# SCH_esp32_2022-05-23.net
KiCad netlist of a schematic drawn in EasyEDA
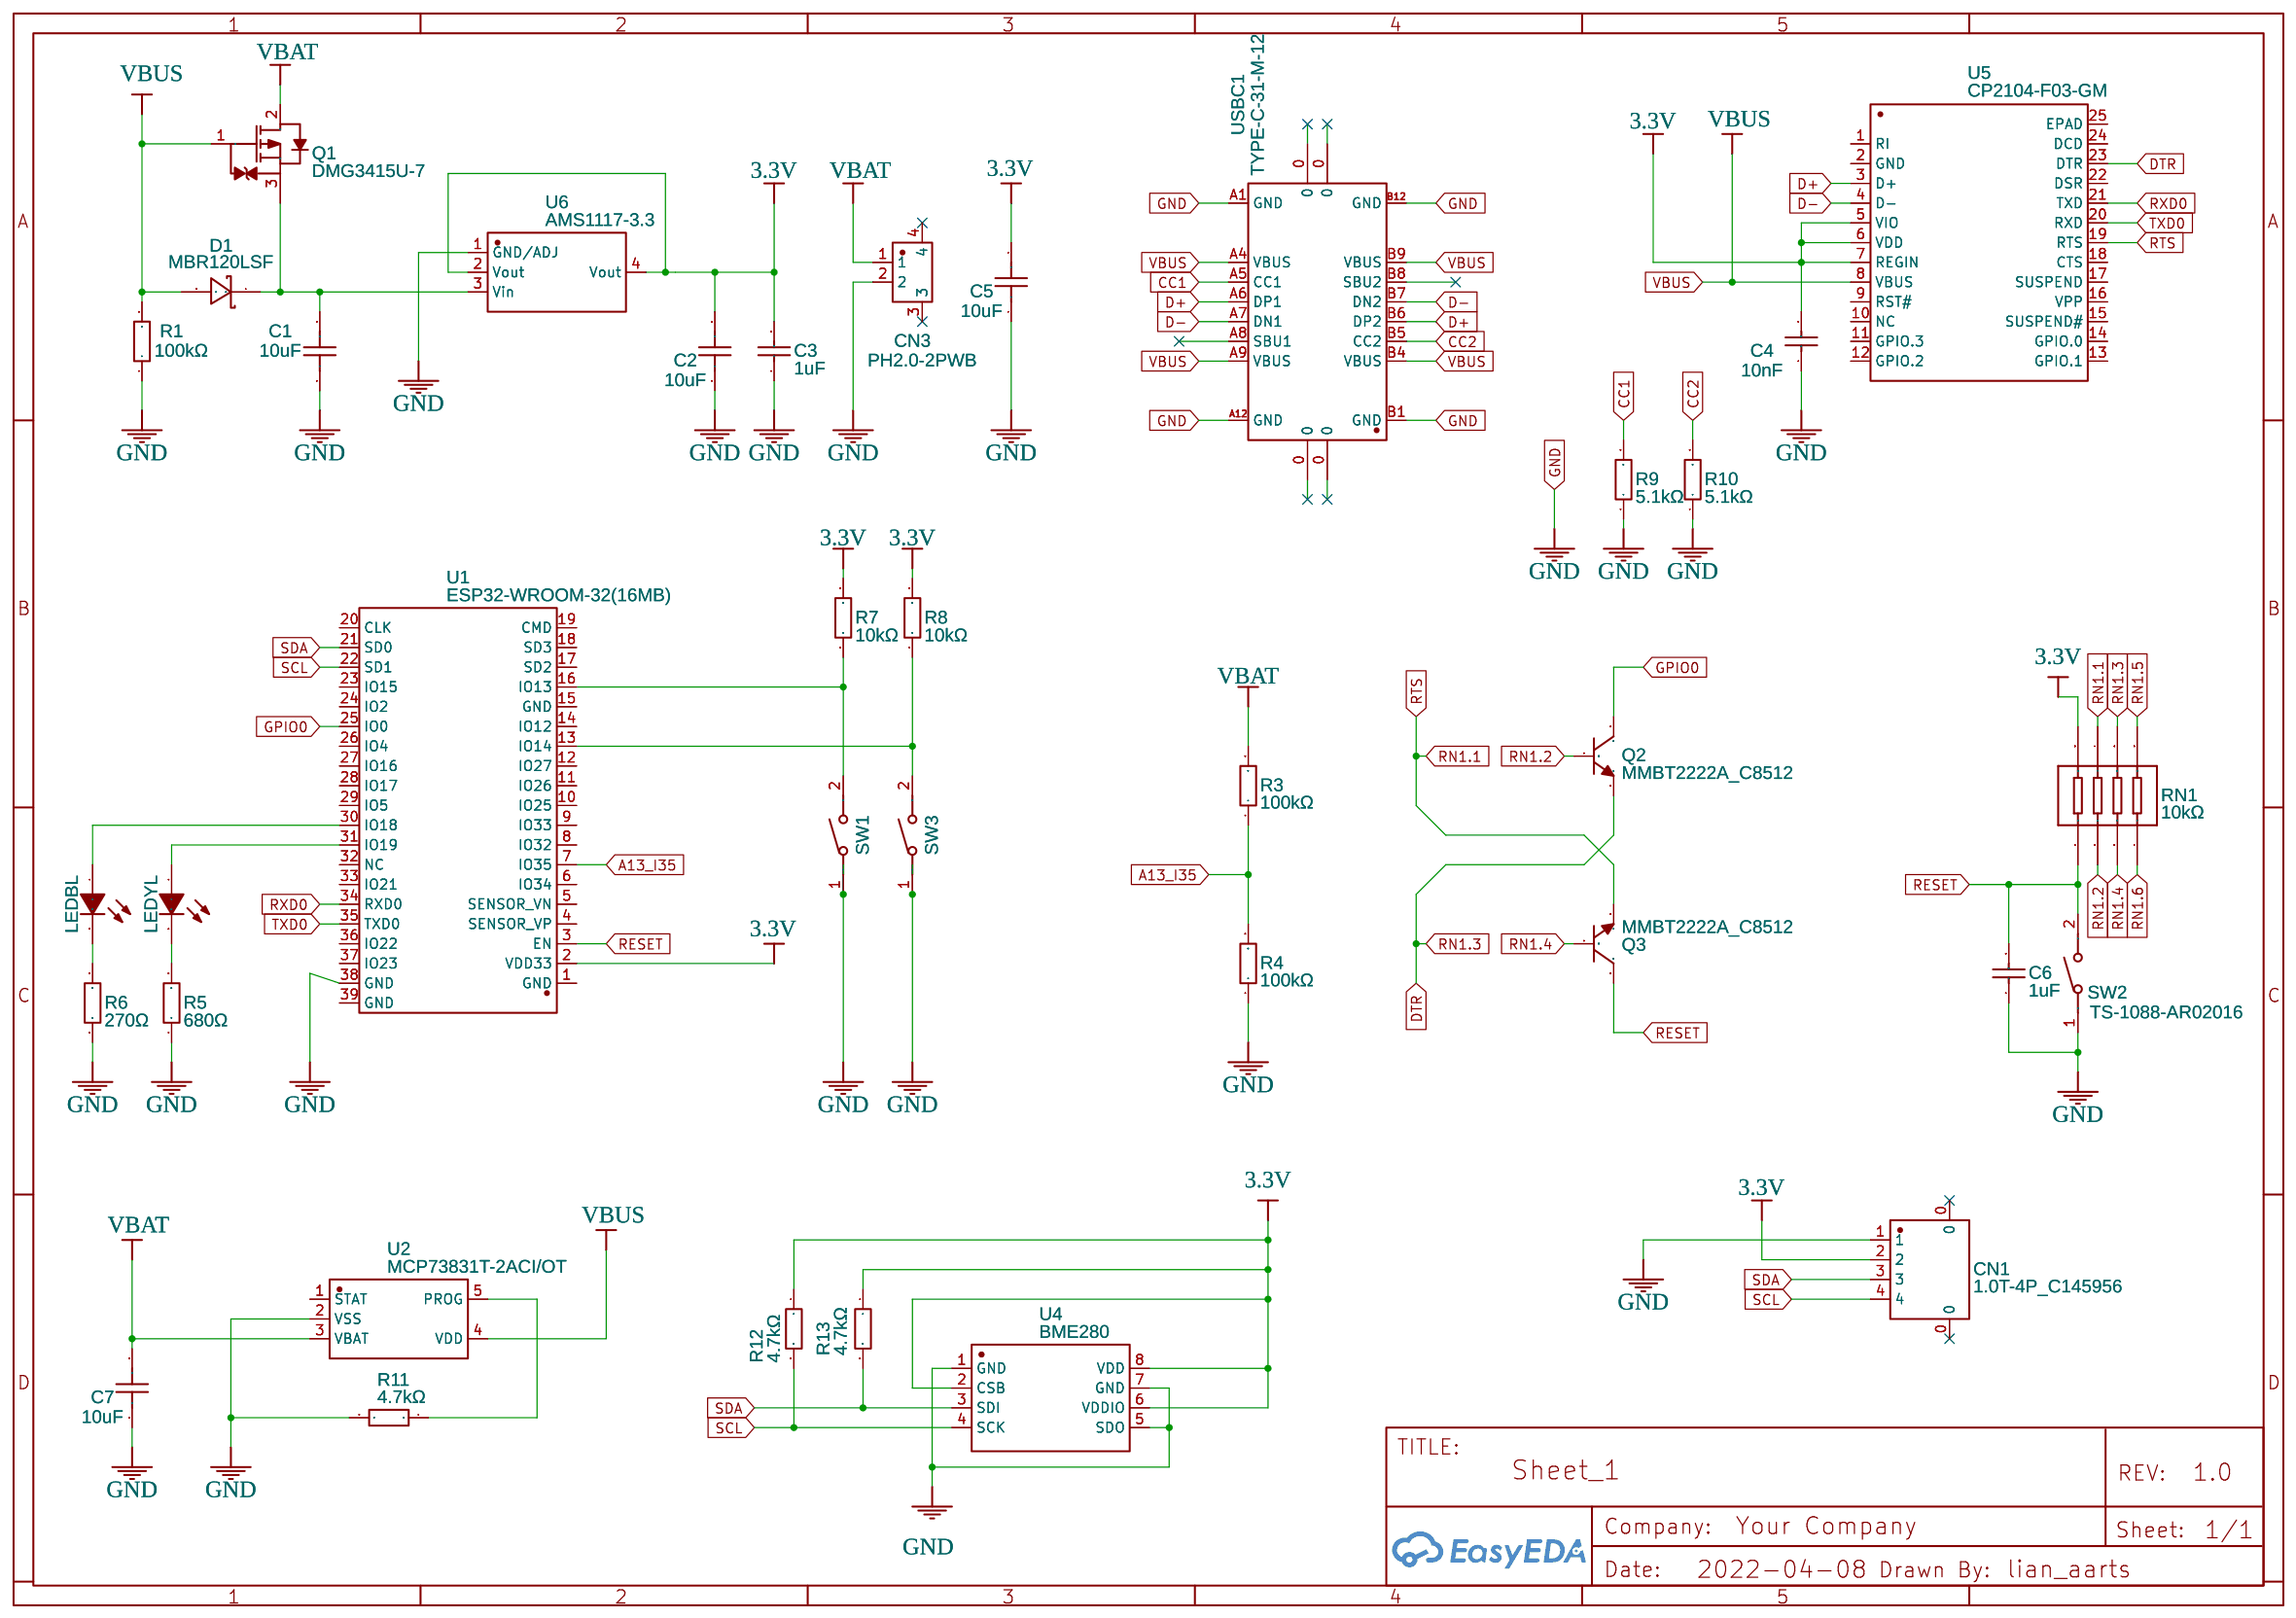
[diagram p0: schematic sheet]

(export (version "E")
  (design (tool "Eeschema 10.0.6"))
  (components
    (comp (ref "C1")
      (value "10uF")
      (fields
        (field (name "BOM_Manufacturer Part") "GRM21BR61H106KE43L")
        (field (name "BOM_Supplier Part") "C440198")
      )
      (libsource (lib "") (part "GRM21BR61H106KE43L"))
    )
    (comp (ref "C2")
      (value "10uF")
      (fields
        (field (name "BOM_Manufacturer Part") "GRM21BR61H106KE43L")
        (field (name "BOM_Supplier Part") "C440198")
      )
      (libsource (lib "") (part "GRM21BR61H106KE43L"))
    )
    (comp (ref "C3")
      (value "1uF")
      (fields
        (field (name "BOM_Manufacturer Part") "CL10A105KB8NNNC")
        (field (name "BOM_Supplier Part") "C15849")
      )
      (libsource (lib "") (part "CL10A105KB8NNNC"))
    )
    (comp (ref "C4")
      (value "10nF")
      (fields
        (field (name "BOM_Manufacturer Part") "CL21B103KBANNNC")
        (field (name "BOM_Supplier Part") "C1710")
      )
      (libsource (lib "") (part "CL21B103KBANNNC"))
    )
    (comp (ref "C5")
      (value "10uF")
      (fields
        (field (name "BOM_Manufacturer Part") "GRM21BR61H106KE43L")
        (field (name "BOM_Supplier Part") "C440198")
      )
      (libsource (lib "") (part "GRM21BR61H106KE43L"))
    )
    (comp (ref "C6")
      (value "1uF")
      (fields
        (field (name "BOM_Manufacturer Part") "CL10A105KB8NNNC")
        (field (name "BOM_Supplier Part") "C15849")
      )
      (libsource (lib "") (part "CL10A105KB8NNNC"))
    )
    (comp (ref "C7")
      (value "10uF")
      (fields
        (field (name "BOM_Manufacturer Part") "GRM21BR61H106KE43L")
        (field (name "BOM_Supplier Part") "C440198")
      )
      (libsource (lib "") (part "GRM21BR61H106KE43L"))
    )
    (comp (ref "CN1")
      (value "1.0T-4P_C145956")
      (fields (field (name "BOM_Supplier Part") "C145956"))
      (libsource (lib "") (part "1.0T-4P_C145956"))
    )
    (comp (ref "CN3")
      (value "PH2.0-2PWB")
      (fields
        (field (name "BOM_Manufacturer Part") "PH2.0-2PWB Horizontal")
        (field (name "BOM_Supplier Part") "C47647")
      )
      (libsource (lib "") (part "PH2.0-2PWB"))
    )
    (comp (ref "D1")
      (value "MBR120LSF")
      (fields (field (name "BOM_Supplier Part") "C130880"))
      (libsource (lib "") (part "MBR120LSF"))
    )
    (comp (ref "LEDBL")
      (value "19-217/BHC-ZL1M2RY/3T")
      (fields (field (name "BOM_Supplier Part") "C72041"))
      (libsource (lib "") (part "19-217/BHC-ZL1M2RY/3T"))
    )
    (comp (ref "LEDYL")
      (value "19-213/Y2C-CQ2R2L/3T(CY)")
      (fields (field (name "BOM_Supplier Part") "C72038"))
      (libsource (lib "") (part "19-213/Y2C-CQ2R2L/3T(CY)"))
    )
    (comp (ref "Q1")
      (value "DMG3415U-7")
      (fields (field (name "BOM_Supplier Part") "C96616"))
      (libsource (lib "") (part "DMG3415U-7"))
    )
    (comp (ref "Q2")
      (value "MMBT2222A_C8512")
      (fields (field (name "BOM_Manufacturer Part") "MMBT2222A") (field (name "BOM_Supplier Part") "C8512"))
      (libsource (lib "") (part "MMBT2222A_C8512"))
    )
    (comp (ref "Q3")
      (value "MMBT2222A_C8512")
      (fields (field (name "BOM_Manufacturer Part") "MMBT2222A") (field (name "BOM_Supplier Part") "C8512"))
      (libsource (lib "") (part "MMBT2222A_C8512_1"))
    )
    (comp (ref "R1")
      (value "100kΩ")
      (fields
        (field (name "BOM_Manufacturer Part") "0603WAF1003T5E")
        (field (name "BOM_Supplier Part") "C25803")
      )
      (libsource (lib "") (part "0603WAF1003T5E"))
    )
    (comp (ref "R3")
      (value "100kΩ")
      (fields
        (field (name "BOM_Manufacturer Part") "0603WAF1003T5E")
        (field (name "BOM_Supplier Part") "C25803")
      )
      (libsource (lib "") (part "0603WAF1003T5E"))
    )
    (comp (ref "R4")
      (value "100kΩ")
      (fields
        (field (name "BOM_Manufacturer Part") "0603WAF1003T5E")
        (field (name "BOM_Supplier Part") "C25803")
      )
      (libsource (lib "") (part "0603WAF1003T5E"))
    )
    (comp (ref "R5")
      (value "680Ω")
      (fields
        (field (name "BOM_Manufacturer Part") "0603WAF6800T5E")
        (field (name "BOM_Supplier Part") "C23228")
      )
      (libsource (lib "") (part "0603WAF6800T5E"))
    )
    (comp (ref "R6")
      (value "270Ω")
      (fields
        (field (name "BOM_Manufacturer Part") "0603WAF2700T5E")
        (field (name "BOM_Supplier Part") "C22966")
      )
      (libsource (lib "") (part "0603WAF2700T5E"))
    )
    (comp (ref "R7")
      (value "10kΩ")
      (fields
        (field (name "BOM_Manufacturer Part") "0603WAF1002T5E")
        (field (name "BOM_Supplier Part") "C25804")
      )
      (libsource (lib "") (part "0603WAF1002T5E"))
    )
    (comp (ref "R8")
      (value "10kΩ")
      (fields
        (field (name "BOM_Manufacturer Part") "0603WAF1002T5E")
        (field (name "BOM_Supplier Part") "C25804")
      )
      (libsource (lib "") (part "0603WAF1002T5E"))
    )
    (comp (ref "R9")
      (value "5.1kΩ")
      (fields
        (field (name "BOM_Manufacturer Part") "0603WAF5101T5E")
        (field (name "BOM_Supplier Part") "C23186")
      )
      (libsource (lib "") (part "0603WAF5101T5E"))
    )
    (comp (ref "R10")
      (value "5.1kΩ")
      (fields
        (field (name "BOM_Manufacturer Part") "0603WAF5101T5E")
        (field (name "BOM_Supplier Part") "C23186")
      )
      (libsource (lib "") (part "0603WAF5101T5E"))
    )
    (comp (ref "R11")
      (value "4.7kΩ")
      (fields
        (field (name "BOM_Manufacturer Part") "0603WAF4701T5E")
        (field (name "BOM_Supplier Part") "C23162")
      )
      (libsource (lib "") (part "0603WAF4701T5E_1"))
    )
    (comp (ref "R12")
      (value "4.7kΩ")
      (fields
        (field (name "BOM_Manufacturer Part") "0603WAF4701T5E")
        (field (name "BOM_Supplier Part") "C23162")
      )
      (libsource (lib "") (part "0603WAF4701T5E"))
    )
    (comp (ref "R13")
      (value "4.7kΩ")
      (fields
        (field (name "BOM_Manufacturer Part") "0603WAF4701T5E")
        (field (name "BOM_Supplier Part") "C23162")
      )
      (libsource (lib "") (part "0603WAF4701T5E"))
    )
    (comp (ref "RN1")
      (value "10kΩ")
      (fields
        (field (name "BOM_Manufacturer Part") "RTA03-4D103JTP")
        (field (name "BOM_Supplier Part") "C102646")
      )
      (libsource (lib "") (part "RTA03-4D103JTP"))
    )
    (comp (ref "SW1")
      (value "TS-1088-AR02016")
      (fields (field (name "BOM_Supplier Part") "C720477"))
      (libsource (lib "") (part "TS-1088-AR02016"))
    )
    (comp (ref "SW2")
      (value "TS-1088-AR02016")
      (fields (field (name "BOM_Supplier Part") "C720477"))
      (libsource (lib "") (part "TS-1088-AR02016"))
    )
    (comp (ref "SW3")
      (value "TS-1088-AR02016")
      (fields (field (name "BOM_Supplier Part") "C720477"))
      (libsource (lib "") (part "TS-1088-AR02016"))
    )
    (comp (ref "U1")
      (value "ESP32-WROOM-32(16MB)")
      (fields (field (name "BOM_Supplier Part") "C529581"))
      (libsource (lib "") (part "ESP32-WROOM-32(16MB)"))
    )
    (comp (ref "U2")
      (value "MCP73831T-2ACI/OT")
      (fields (field (name "BOM_Supplier Part") "C424093"))
      (libsource (lib "") (part "MCP73831T-2ACI/OT"))
    )
    (comp (ref "U4")
      (value "BME280")
      (fields (field (name "BOM_Supplier Part") "C92489"))
      (libsource (lib "") (part "BME280"))
    )
    (comp (ref "U5")
      (value "CP2104-F03-GM")
      (fields (field (name "BOM_Supplier Part") "C47742"))
      (libsource (lib "") (part "CP2104-F03-GM"))
    )
    (comp (ref "U6")
      (value "AMS1117-3.3")
      (fields (field (name "BOM_Supplier Part") "C6186"))
      (libsource (lib "") (part "AMS1117-3.3"))
    )
    (comp (ref "USBC1")
      (value "TYPE-C-31-M-12")
      (fields (field (name "BOM_Supplier Part") "C165948"))
      (libsource (lib "") (part "TYPE-C-31-M-12"))
    )
  )
  (nets
    (net (code "1") (name "3.3V") (class "Default")
      (node (ref "C2") (pin "2") (pinfunction "2_2") (pintype "unspecified"))
      (node (ref "C3") (pin "2") (pinfunction "2_2") (pintype "input"))
      (node (ref "C4") (pin "2") (pinfunction "2_2") (pintype "input"))
      (node (ref "C5") (pin "2") (pinfunction "2_2") (pintype "unspecified"))
      (node (ref "CN1") (pin "2") (pinfunction "2_2") (pintype "unspecified"))
      (node (ref "R12") (pin "1") (pinfunction "1_1") (pintype "input"))
      (node (ref "R13") (pin "1") (pinfunction "1_1") (pintype "input"))
      (node (ref "R7") (pin "2") (pinfunction "2_2") (pintype "input"))
      (node (ref "R8") (pin "2") (pinfunction "2_2") (pintype "input"))
      (node (ref "RN1") (pin "8") (pinfunction "8_8") (pintype "input"))
      (node (ref "U1") (pin "2") (pinfunction "VDD33_2") (pintype "unspecified"))
      (node (ref "U4") (pin "2") (pinfunction "CSB_2") (pintype "unspecified"))
      (node (ref "U4") (pin "6") (pinfunction "VDDIO_6") (pintype "unspecified"))
      (node (ref "U4") (pin "8") (pinfunction "VDD_8") (pintype "unspecified"))
      (node (ref "U5") (pin "5") (pinfunction "VIO_5") (pintype "unspecified"))
      (node (ref "U5") (pin "6") (pinfunction "VDD_6") (pintype "unspecified"))
      (node (ref "U5") (pin "7") (pinfunction "REGIN_7") (pintype "unspecified"))
      (node (ref "U6") (pin "2") (pinfunction "Vout_2") (pintype "unspecified"))
      (node (ref "U6") (pin "4") (pinfunction "Vout_4") (pintype "unspecified"))
    )
    (net (code "2") (name "A13_I35") (class "Default")
      (node (ref "R3") (pin "1") (pinfunction "1_1") (pintype "input"))
      (node (ref "R4") (pin "2") (pinfunction "2_2") (pintype "input"))
      (node (ref "U1") (pin "7") (pinfunction "IO35_7") (pintype "unspecified"))
    )
    (net (code "3") (name "CC1") (class "Default")
      (node (ref "R9") (pin "2") (pinfunction "2_2") (pintype "input"))
      (node (ref "USBC1") (pin "A5") (pinfunction "CC1_A5") (pintype "unspecified"))
    )
    (net (code "4") (name "CC2") (class "Default")
      (node (ref "R10") (pin "2") (pinfunction "2_2") (pintype "input"))
      (node (ref "USBC1") (pin "B5") (pinfunction "CC2_B5") (pintype "unspecified"))
    )
    (net (code "5") (name "D+") (class "Default")
      (node (ref "U5") (pin "3") (pinfunction "D+_3") (pintype "unspecified"))
      (node (ref "USBC1") (pin "A6") (pinfunction "DP1_A6") (pintype "unspecified"))
      (node (ref "USBC1") (pin "B6") (pinfunction "DP2_B6") (pintype "unspecified"))
    )
    (net (code "6") (name "D-") (class "Default")
      (node (ref "U5") (pin "4") (pinfunction "D-_4") (pintype "unspecified"))
      (node (ref "USBC1") (pin "A7") (pinfunction "DN1_A7") (pintype "unspecified"))
      (node (ref "USBC1") (pin "B7") (pinfunction "DN2_B7") (pintype "unspecified"))
    )
    (net (code "7") (name "DTR") (class "Default")
      (node (ref "Q2") (pin "2") (pinfunction "E_2") (pintype "unspecified"))
      (node (ref "RN1") (pin "6") (pinfunction "6_6") (pintype "input"))
      (node (ref "U5") (pin "23") (pinfunction "DTR_23") (pintype "unspecified"))
    )
    (net (code "8") (name "GND") (class "Default")
      (node (ref "C1") (pin "1") (pinfunction "1_1") (pintype "unspecified"))
      (node (ref "C2") (pin "1") (pinfunction "1_1") (pintype "unspecified"))
      (node (ref "C3") (pin "1") (pinfunction "1_1") (pintype "input"))
      (node (ref "C4") (pin "1") (pinfunction "1_1") (pintype "input"))
      (node (ref "C5") (pin "1") (pinfunction "1_1") (pintype "unspecified"))
      (node (ref "C6") (pin "1") (pinfunction "1_1") (pintype "input"))
      (node (ref "C7") (pin "1") (pinfunction "1_1") (pintype "unspecified"))
      (node (ref "CN1") (pin "1") (pinfunction "1_1") (pintype "unspecified"))
      (node (ref "CN3") (pin "2") (pinfunction "2_2") (pintype "unspecified"))
      (node (ref "R1") (pin "1") (pinfunction "1_1") (pintype "input"))
      (node (ref "R10") (pin "1") (pinfunction "1_1") (pintype "input"))
      (node (ref "R11") (pin "2") (pinfunction "2_2") (pintype "input"))
      (node (ref "R4") (pin "1") (pinfunction "1_1") (pintype "input"))
      (node (ref "R5") (pin "1") (pinfunction "1_1") (pintype "input"))
      (node (ref "R6") (pin "1") (pinfunction "1_1") (pintype "input"))
      (node (ref "R9") (pin "1") (pinfunction "1_1") (pintype "input"))
      (node (ref "SW1") (pin "1") (pinfunction "1_1") (pintype "unspecified"))
      (node (ref "SW2") (pin "1") (pinfunction "1_1") (pintype "unspecified"))
      (node (ref "SW3") (pin "1") (pinfunction "1_1") (pintype "unspecified"))
      (node (ref "U1") (pin "38") (pinfunction "GND_38") (pintype "unspecified"))
      (node (ref "U2") (pin "2") (pinfunction "VSS_2") (pintype "unspecified"))
      (node (ref "U4") (pin "1") (pinfunction "GND_1") (pintype "unspecified"))
      (node (ref "U4") (pin "5") (pinfunction "SDO_5") (pintype "unspecified"))
      (node (ref "U4") (pin "7") (pinfunction "GND_7") (pintype "unspecified"))
      (node (ref "U6") (pin "1") (pinfunction "GND/ADJ_1") (pintype "unspecified"))
      (node (ref "USBC1") (pin "A1") (pinfunction "GND_A1") (pintype "unspecified"))
      (node (ref "USBC1") (pin "A12") (pinfunction "GND_A12") (pintype "unspecified"))
      (node (ref "USBC1") (pin "B1") (pinfunction "GND_B1") (pintype "unspecified"))
      (node (ref "USBC1") (pin "B12") (pinfunction "GND_B12") (pintype "unspecified"))
    )
    (net (code "9") (name "GPIO0") (class "Default")
      (node (ref "Q2") (pin "3") (pinfunction "C_3") (pintype "unspecified"))
      (node (ref "U1") (pin "25") (pinfunction "IO0_25") (pintype "unspecified"))
    )
    (net (code "10") (name "Net-(D1-C)") (class "Default")
      (node (ref "C1") (pin "2") (pinfunction "2_2") (pintype "unspecified"))
      (node (ref "D1") (pin "1") (pinfunction "C_1") (pintype "unspecified"))
      (node (ref "Q1") (pin "3") (pinfunction "S_3") (pintype "unspecified"))
      (node (ref "U6") (pin "3") (pinfunction "Vin_3") (pintype "unspecified"))
    )
    (net (code "11") (name "Net-(LEDBL-A)") (class "Default")
      (node (ref "LEDBL") (pin "1") (pinfunction "A_1") (pintype "input"))
      (node (ref "U1") (pin "30") (pinfunction "IO18_30") (pintype "unspecified"))
    )
    (net (code "12") (name "Net-(LEDBL-C)") (class "Default")
      (node (ref "LEDBL") (pin "2") (pinfunction "C_2") (pintype "input"))
      (node (ref "R6") (pin "2") (pinfunction "2_2") (pintype "input"))
    )
    (net (code "13") (name "Net-(LEDYL-A)") (class "Default")
      (node (ref "LEDYL") (pin "1") (pinfunction "A_1") (pintype "input"))
      (node (ref "U1") (pin "31") (pinfunction "IO19_31") (pintype "unspecified"))
    )
    (net (code "14") (name "Net-(LEDYL-C)") (class "Default")
      (node (ref "LEDYL") (pin "2") (pinfunction "C_2") (pintype "input"))
      (node (ref "R5") (pin "2") (pinfunction "2_2") (pintype "input"))
    )
    (net (code "15") (name "Net-(U1-IO13)") (class "Default")
      (node (ref "R7") (pin "1") (pinfunction "1_1") (pintype "input"))
      (node (ref "SW1") (pin "2") (pinfunction "2_2") (pintype "unspecified"))
      (node (ref "U1") (pin "16") (pinfunction "IO13_16") (pintype "unspecified"))
    )
    (net (code "16") (name "Net-(U1-IO14)") (class "Default")
      (node (ref "R8") (pin "1") (pinfunction "1_1") (pintype "input"))
      (node (ref "SW3") (pin "2") (pinfunction "2_2") (pintype "unspecified"))
      (node (ref "U1") (pin "13") (pinfunction "IO14_13") (pintype "unspecified"))
    )
    (net (code "17") (name "Net-(U2-PROG)") (class "Default")
      (node (ref "R11") (pin "1") (pinfunction "1_1") (pintype "input"))
      (node (ref "U2") (pin "5") (pinfunction "PROG_5") (pintype "unspecified"))
    )
    (net (code "18") (name "RESET") (class "Default")
      (node (ref "C6") (pin "2") (pinfunction "2_2") (pintype "input"))
      (node (ref "Q3") (pin "3") (pinfunction "C_3") (pintype "unspecified"))
      (node (ref "RN1") (pin "1") (pinfunction "1_1") (pintype "input"))
      (node (ref "SW2") (pin "2") (pinfunction "2_2") (pintype "unspecified"))
      (node (ref "U1") (pin "3") (pinfunction "EN_3") (pintype "unspecified"))
    )
    (net (code "19") (name "RN1.1") (class "Default")
      (node (ref "Q3") (pin "2") (pinfunction "E_2") (pintype "unspecified"))
      (node (ref "RN1") (pin "7") (pinfunction "7_7") (pintype "input"))
      (node (ref "U5") (pin "19") (pinfunction "RTS_19") (pintype "unspecified"))
    )
    (net (code "20") (name "RN1.2") (class "Default")
      (node (ref "Q2") (pin "1") (pinfunction "B_1") (pintype "unspecified"))
      (node (ref "RN1") (pin "2") (pinfunction "2_2") (pintype "input"))
    )
    (net (code "21") (name "RN1.4") (class "Default")
      (node (ref "Q3") (pin "1") (pinfunction "B_1") (pintype "unspecified"))
      (node (ref "RN1") (pin "3") (pinfunction "3_3") (pintype "input"))
    )
    (net (code "22") (name "RN1.5") (class "Default")
      (node (ref "RN1") (pin "5") (pinfunction "5_5") (pintype "input"))
    )
    (net (code "23") (name "RN1.6") (class "Default")
      (node (ref "RN1") (pin "4") (pinfunction "4_4") (pintype "input"))
    )
    (net (code "24") (name "RXD0") (class "Default")
      (node (ref "U1") (pin "34") (pinfunction "RXD0_34") (pintype "unspecified"))
      (node (ref "U5") (pin "21") (pinfunction "TXD_21") (pintype "unspecified"))
    )
    (net (code "25") (name "SCL") (class "Default")
      (node (ref "CN1") (pin "4") (pinfunction "4_4") (pintype "unspecified"))
      (node (ref "R12") (pin "2") (pinfunction "2_2") (pintype "input"))
      (node (ref "U1") (pin "22") (pinfunction "SD1_22") (pintype "unspecified"))
      (node (ref "U4") (pin "4") (pinfunction "SCK_4") (pintype "unspecified"))
    )
    (net (code "26") (name "SDA") (class "Default")
      (node (ref "CN1") (pin "3") (pinfunction "3_3") (pintype "unspecified"))
      (node (ref "R13") (pin "2") (pinfunction "2_2") (pintype "input"))
      (node (ref "U1") (pin "21") (pinfunction "SD0_21") (pintype "unspecified"))
      (node (ref "U4") (pin "3") (pinfunction "SDI_3") (pintype "unspecified"))
    )
    (net (code "27") (name "TXD0") (class "Default")
      (node (ref "U1") (pin "35") (pinfunction "TXD0_35") (pintype "unspecified"))
      (node (ref "U5") (pin "20") (pinfunction "RXD_20") (pintype "unspecified"))
    )
    (net (code "28") (name "VBAT") (class "Default")
      (node (ref "C7") (pin "2") (pinfunction "2_2") (pintype "unspecified"))
      (node (ref "CN3") (pin "1") (pinfunction "1_1") (pintype "unspecified"))
      (node (ref "Q1") (pin "2") (pinfunction "D_2") (pintype "unspecified"))
      (node (ref "R3") (pin "2") (pinfunction "2_2") (pintype "input"))
      (node (ref "U2") (pin "3") (pinfunction "VBAT_3") (pintype "unspecified"))
    )
    (net (code "29") (name "VBUS") (class "Default")
      (node (ref "D1") (pin "2") (pinfunction "A_2") (pintype "unspecified"))
      (node (ref "Q1") (pin "1") (pinfunction "G_1") (pintype "unspecified"))
      (node (ref "R1") (pin "2") (pinfunction "2_2") (pintype "input"))
      (node (ref "U2") (pin "4") (pinfunction "VDD_4") (pintype "unspecified"))
      (node (ref "U5") (pin "8") (pinfunction "VBUS_8") (pintype "unspecified"))
      (node (ref "USBC1") (pin "A4") (pinfunction "VBUS_A4") (pintype "unspecified"))
      (node (ref "USBC1") (pin "A9") (pinfunction "VBUS_A9") (pintype "unspecified"))
      (node (ref "USBC1") (pin "B4") (pinfunction "VBUS_B4") (pintype "unspecified"))
      (node (ref "USBC1") (pin "B9") (pinfunction "VBUS_B9") (pintype "unspecified"))
    )
    (net (code "30") (name "unconnected-(CN1-Pad0)") (class "Default")
      (node (ref "CN1") (pin "0") (pinfunction "0_0") (pintype "unspecified+no_connect"))
    )
    (net (code "31") (name "unconnected-(CN1-Pad0)_1") (class "Default")
      (node (ref "CN1") (pin "0") (pinfunction "0_0") (pintype "unspecified+no_connect"))
    )
    (net (code "32") (name "unconnected-(CN3-Pad3)") (class "Default")
      (node (ref "CN3") (pin "3") (pinfunction "3_3") (pintype "unspecified+no_connect"))
    )
    (net (code "33") (name "unconnected-(CN3-Pad4)") (class "Default")
      (node (ref "CN3") (pin "4") (pinfunction "4_4") (pintype "unspecified+no_connect"))
    )
    (net (code "34") (name "unconnected-(U1-CLK-Pad20)") (class "Default")
      (node (ref "U1") (pin "20") (pinfunction "CLK_20") (pintype "unspecified"))
    )
    (net (code "35") (name "unconnected-(U1-CMD-Pad19)") (class "Default")
      (node (ref "U1") (pin "19") (pinfunction "CMD_19") (pintype "unspecified"))
    )
    (net (code "36") (name "unconnected-(U1-GND-Pad1)") (class "Default")
      (node (ref "U1") (pin "1") (pinfunction "GND_1") (pintype "unspecified"))
    )
    (net (code "37") (name "unconnected-(U1-GND-Pad15)") (class "Default")
      (node (ref "U1") (pin "15") (pinfunction "GND_15") (pintype "unspecified"))
    )
    (net (code "38") (name "unconnected-(U1-GND-Pad39)") (class "Default")
      (node (ref "U1") (pin "39") (pinfunction "GND_39") (pintype "unspecified"))
    )
    (net (code "39") (name "unconnected-(U1-IO2-Pad24)") (class "Default")
      (node (ref "U1") (pin "24") (pinfunction "IO2_24") (pintype "unspecified"))
    )
    (net (code "40") (name "unconnected-(U1-IO4-Pad26)") (class "Default")
      (node (ref "U1") (pin "26") (pinfunction "IO4_26") (pintype "unspecified"))
    )
    (net (code "41") (name "unconnected-(U1-IO5-Pad29)") (class "Default")
      (node (ref "U1") (pin "29") (pinfunction "IO5_29") (pintype "unspecified"))
    )
    (net (code "42") (name "unconnected-(U1-IO12-Pad14)") (class "Default")
      (node (ref "U1") (pin "14") (pinfunction "IO12_14") (pintype "unspecified"))
    )
    (net (code "43") (name "unconnected-(U1-IO15-Pad23)") (class "Default")
      (node (ref "U1") (pin "23") (pinfunction "IO15_23") (pintype "unspecified"))
    )
    (net (code "44") (name "unconnected-(U1-IO16-Pad27)") (class "Default")
      (node (ref "U1") (pin "27") (pinfunction "IO16_27") (pintype "unspecified"))
    )
    (net (code "45") (name "unconnected-(U1-IO17-Pad28)") (class "Default")
      (node (ref "U1") (pin "28") (pinfunction "IO17_28") (pintype "unspecified"))
    )
    (net (code "46") (name "unconnected-(U1-IO21-Pad33)") (class "Default")
      (node (ref "U1") (pin "33") (pinfunction "IO21_33") (pintype "unspecified"))
    )
    (net (code "47") (name "unconnected-(U1-IO22-Pad36)") (class "Default")
      (node (ref "U1") (pin "36") (pinfunction "IO22_36") (pintype "unspecified"))
    )
    (net (code "48") (name "unconnected-(U1-IO23-Pad37)") (class "Default")
      (node (ref "U1") (pin "37") (pinfunction "IO23_37") (pintype "unspecified"))
    )
    (net (code "49") (name "unconnected-(U1-IO25-Pad10)") (class "Default")
      (node (ref "U1") (pin "10") (pinfunction "IO25_10") (pintype "unspecified"))
    )
    (net (code "50") (name "unconnected-(U1-IO26-Pad11)") (class "Default")
      (node (ref "U1") (pin "11") (pinfunction "IO26_11") (pintype "unspecified"))
    )
    (net (code "51") (name "unconnected-(U1-IO27-Pad12)") (class "Default")
      (node (ref "U1") (pin "12") (pinfunction "IO27_12") (pintype "unspecified"))
    )
    (net (code "52") (name "unconnected-(U1-IO32-Pad8)") (class "Default")
      (node (ref "U1") (pin "8") (pinfunction "IO32_8") (pintype "unspecified"))
    )
    (net (code "53") (name "unconnected-(U1-IO33-Pad9)") (class "Default")
      (node (ref "U1") (pin "9") (pinfunction "IO33_9") (pintype "unspecified"))
    )
    (net (code "54") (name "unconnected-(U1-IO34-Pad6)") (class "Default")
      (node (ref "U1") (pin "6") (pinfunction "IO34_6") (pintype "unspecified"))
    )
    (net (code "55") (name "unconnected-(U1-NC-Pad32)") (class "Default")
      (node (ref "U1") (pin "32") (pinfunction "NC_32") (pintype "unspecified"))
    )
    (net (code "56") (name "unconnected-(U1-SD2-Pad17)") (class "Default")
      (node (ref "U1") (pin "17") (pinfunction "SD2_17") (pintype "unspecified"))
    )
    (net (code "57") (name "unconnected-(U1-SD3-Pad18)") (class "Default")
      (node (ref "U1") (pin "18") (pinfunction "SD3_18") (pintype "unspecified"))
    )
    (net (code "58") (name "unconnected-(U1-SENSOR_VN-Pad5)") (class "Default")
      (node (ref "U1") (pin "5") (pinfunction "SENSOR_VN_5") (pintype "unspecified"))
    )
    (net (code "59") (name "unconnected-(U1-SENSOR_VP-Pad4)") (class "Default")
      (node (ref "U1") (pin "4") (pinfunction "SENSOR_VP_4") (pintype "unspecified"))
    )
    (net (code "60") (name "unconnected-(U2-STAT-Pad1)") (class "Default")
      (node (ref "U2") (pin "1") (pinfunction "STAT_1") (pintype "unspecified"))
    )
    (net (code "61") (name "unconnected-(U5-CTS-Pad18)") (class "Default")
      (node (ref "U5") (pin "18") (pinfunction "CTS_18") (pintype "unspecified"))
    )
    (net (code "62") (name "unconnected-(U5-DCD-Pad24)") (class "Default")
      (node (ref "U5") (pin "24") (pinfunction "DCD_24") (pintype "unspecified"))
    )
    (net (code "63") (name "unconnected-(U5-DSR-Pad22)") (class "Default")
      (node (ref "U5") (pin "22") (pinfunction "DSR_22") (pintype "unspecified"))
    )
    (net (code "64") (name "unconnected-(U5-EPAD-Pad25)") (class "Default")
      (node (ref "U5") (pin "25") (pinfunction "EPAD_25") (pintype "unspecified"))
    )
    (net (code "65") (name "unconnected-(U5-GND-Pad2)") (class "Default")
      (node (ref "U5") (pin "2") (pinfunction "GND_2") (pintype "unspecified"))
    )
    (net (code "66") (name "unconnected-(U5-GPIO.0-Pad14)") (class "Default")
      (node (ref "U5") (pin "14") (pinfunction "GPIO.0_14") (pintype "unspecified"))
    )
    (net (code "67") (name "unconnected-(U5-GPIO.1-Pad13)") (class "Default")
      (node (ref "U5") (pin "13") (pinfunction "GPIO.1_13") (pintype "unspecified"))
    )
    (net (code "68") (name "unconnected-(U5-GPIO.2-Pad12)") (class "Default")
      (node (ref "U5") (pin "12") (pinfunction "GPIO.2_12") (pintype "unspecified"))
    )
    (net (code "69") (name "unconnected-(U5-GPIO.3-Pad11)") (class "Default")
      (node (ref "U5") (pin "11") (pinfunction "GPIO.3_11") (pintype "unspecified"))
    )
    (net (code "70") (name "unconnected-(U5-NC-Pad10)") (class "Default")
      (node (ref "U5") (pin "10") (pinfunction "NC_10") (pintype "unspecified"))
    )
    (net (code "71") (name "unconnected-(U5-RI-Pad1)") (class "Default")
      (node (ref "U5") (pin "1") (pinfunction "RI_1") (pintype "unspecified"))
    )
    (net (code "72") (name "unconnected-(U5-RST#-Pad9)") (class "Default")
      (node (ref "U5") (pin "9") (pinfunction "RST#_9") (pintype "unspecified"))
    )
    (net (code "73") (name "unconnected-(U5-SUSPEND#-Pad15)") (class "Default")
      (node (ref "U5") (pin "15") (pinfunction "SUSPEND#_15") (pintype "unspecified"))
    )
    (net (code "74") (name "unconnected-(U5-SUSPEND-Pad17)") (class "Default")
      (node (ref "U5") (pin "17") (pinfunction "SUSPEND_17") (pintype "unspecified"))
    )
    (net (code "75") (name "unconnected-(U5-VPP-Pad16)") (class "Default")
      (node (ref "U5") (pin "16") (pinfunction "VPP_16") (pintype "unspecified"))
    )
    (net (code "76") (name "unconnected-(USBC1-Pad0)") (class "Default")
      (node (ref "USBC1") (pin "0") (pinfunction "0_0") (pintype "unspecified+no_connect"))
    )
    (net (code "77") (name "unconnected-(USBC1-Pad0)_1") (class "Default")
      (node (ref "USBC1") (pin "0") (pinfunction "0_0") (pintype "unspecified+no_connect"))
    )
    (net (code "78") (name "unconnected-(USBC1-Pad0)_2") (class "Default")
      (node (ref "USBC1") (pin "0") (pinfunction "0_0") (pintype "unspecified+no_connect"))
    )
    (net (code "79") (name "unconnected-(USBC1-Pad0)_3") (class "Default")
      (node (ref "USBC1") (pin "0") (pinfunction "0_0") (pintype "unspecified+no_connect"))
    )
    (net (code "80") (name "unconnected-(USBC1-SBU1-PadA8)") (class "Default")
      (node (ref "USBC1") (pin "A8") (pinfunction "SBU1_A8") (pintype "unspecified+no_connect"))
    )
    (net (code "81") (name "unconnected-(USBC1-SBU2-PadB8)") (class "Default")
      (node (ref "USBC1") (pin "B8") (pinfunction "SBU2_B8") (pintype "unspecified+no_connect"))
    )
  )
)
